# edge_dff_rst_active.net
KiCad netlist of a schematic drawn in Altium Designer
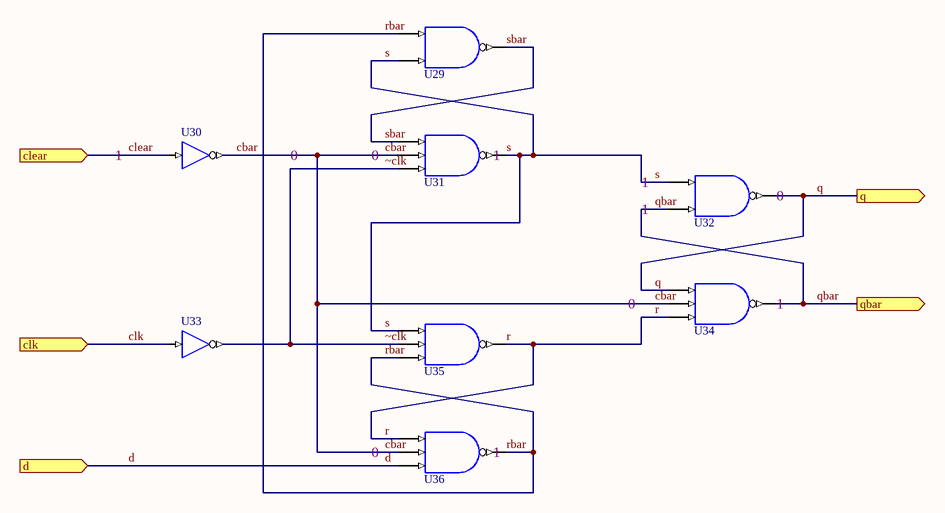
[diagram p0: edge_dff_rst_active.SchDoc]

(export (version "E")
  (design (tool "Eeschema 10.0.6"))
  (components
    (comp (ref "U29")
      (value "AND 2")
      (description "2 Input AND")
      (libsource (lib "BlockSchematics") (part "AND_2"))
    )
    (comp (ref "U30")
      (value "BUF_inv")
      (description "1-bit General Purpose (Non-inverting) Buffer")
      (libsource (lib "BlockSchematics") (part "BUF_inv"))
    )
    (comp (ref "U31")
      (value "NAND_3")
      (description "3 Input NAND 1 Not")
      (libsource (lib "BlockSchematics") (part "NAND_3"))
    )
    (comp (ref "U32")
      (value "AND 2")
      (description "2 Input AND")
      (libsource (lib "BlockSchematics") (part "AND_2"))
    )
    (comp (ref "U33")
      (value "BUF_inv")
      (description "1-bit General Purpose (Non-inverting) Buffer")
      (libsource (lib "BlockSchematics") (part "BUF_inv"))
    )
    (comp (ref "U34")
      (value "NAND_3")
      (description "3 Input NAND 1 Not")
      (libsource (lib "BlockSchematics") (part "NAND_3"))
    )
    (comp (ref "U35")
      (value "NAND_3")
      (description "3 Input NAND 1 Not")
      (libsource (lib "BlockSchematics") (part "NAND_3"))
    )
    (comp (ref "U36")
      (value "NAND_3")
      (description "3 Input NAND 1 Not")
      (libsource (lib "BlockSchematics") (part "NAND_3"))
    )
  )
  (nets
    (net (code "1") (name "/cbar") (class "Default")
      (node (ref "U30") (pin "O") (pinfunction "O_O") (pintype "output"))
      (node (ref "U31") (pin "B") (pinfunction "B_B") (pintype "input"))
      (node (ref "U34") (pin "B") (pinfunction "B_B") (pintype "input"))
      (node (ref "U36") (pin "B") (pinfunction "B_B") (pintype "input"))
    )
    (net (code "2") (name "/clear") (class "Default")
      (node (ref "U30") (pin "I") (pinfunction "I_I") (pintype "input"))
    )
    (net (code "3") (name "/clk") (class "Default")
      (node (ref "U33") (pin "I") (pinfunction "I_I") (pintype "input"))
    )
    (net (code "4") (name "/d") (class "Default")
      (node (ref "U36") (pin "C") (pinfunction "C_C") (pintype "input"))
    )
    (net (code "5") (name "/q") (class "Default")
      (node (ref "U32") (pin "Y") (pinfunction "Y_Y") (pintype "output"))
      (node (ref "U34") (pin "A") (pinfunction "A_A") (pintype "input"))
    )
    (net (code "6") (name "/qbar") (class "Default")
      (node (ref "U32") (pin "B") (pinfunction "B_B") (pintype "input"))
      (node (ref "U34") (pin "Y") (pinfunction "Y_Y") (pintype "output"))
    )
    (net (code "7") (name "/r") (class "Default")
      (node (ref "U34") (pin "C") (pinfunction "C_C") (pintype "input"))
      (node (ref "U35") (pin "Y") (pinfunction "Y_Y") (pintype "output"))
      (node (ref "U36") (pin "A") (pinfunction "A_A") (pintype "input"))
    )
    (net (code "8") (name "/rbar") (class "Default")
      (node (ref "U29") (pin "A") (pinfunction "A_A") (pintype "input"))
      (node (ref "U35") (pin "C") (pinfunction "C_C") (pintype "input"))
      (node (ref "U36") (pin "Y") (pinfunction "Y_Y") (pintype "output"))
    )
    (net (code "9") (name "/s") (class "Default")
      (node (ref "U29") (pin "B") (pinfunction "B_B") (pintype "input"))
      (node (ref "U31") (pin "Y") (pinfunction "Y_Y") (pintype "output"))
      (node (ref "U32") (pin "A") (pinfunction "A_A") (pintype "input"))
      (node (ref "U35") (pin "A") (pinfunction "A_A") (pintype "input"))
    )
    (net (code "10") (name "/sbar") (class "Default")
      (node (ref "U29") (pin "Y") (pinfunction "Y_Y") (pintype "output"))
      (node (ref "U31") (pin "A") (pinfunction "A_A") (pintype "input"))
    )
    (net (code "11") (name "/~clk") (class "Default")
      (node (ref "U31") (pin "C") (pinfunction "C_C") (pintype "input"))
      (node (ref "U33") (pin "O") (pinfunction "O_O") (pintype "output"))
      (node (ref "U35") (pin "B") (pinfunction "B_B") (pintype "input"))
    )
  )
)
